# Pole_Position.net
KiCad netlist of a schematic drawn in Altium Designer
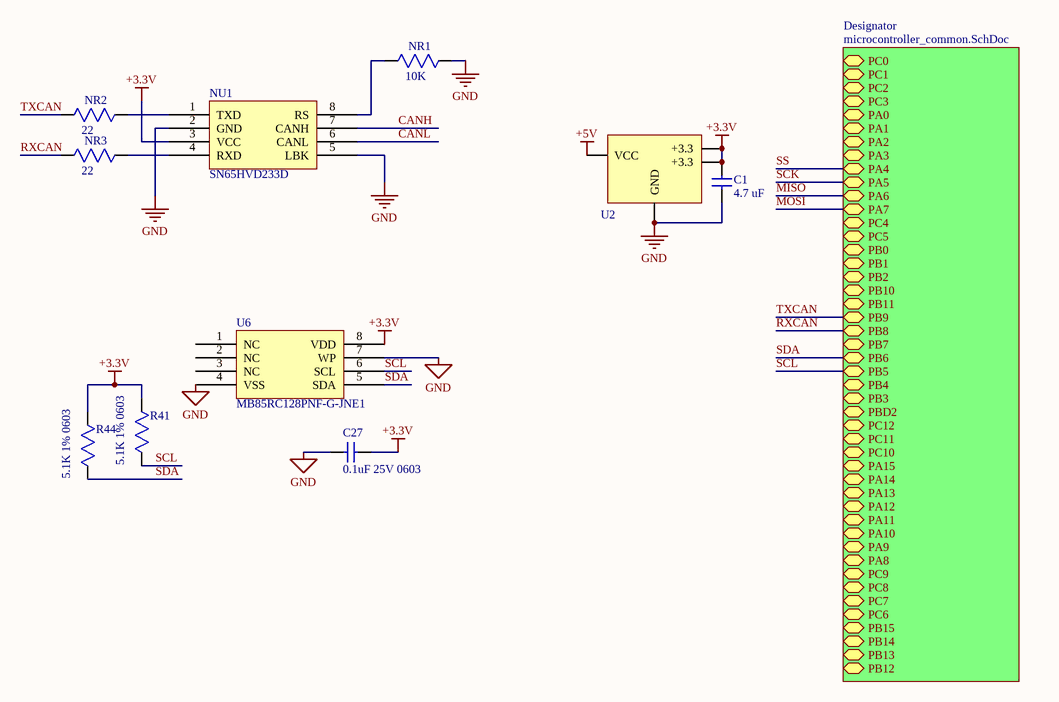
[diagram p0: Pole Position.SchDoc]

(export (version "E")
  (design (tool "Eeschema 10.0.6"))
  (components
    (comp (ref "C1")
      (value "4.7 uF")
      (footprint "0805_Capacitor")
      (description "CAP CER 4.7UF 50V X5R 10% 0805")
      (fields
        (field (name "MANUFACTURER") "TDK Corp")
        (field (name "Comment") "CAP 4.7uF")
        (field (name "SVP CREATOR") "Matt Rogge")
      )
      (libsource (lib "d1_SchLib") (part "C_0805_4.7uF"))
    )
    (comp (ref "C27")
      (value "0.1uF 25V 0603")
      (footprint "0603_cap")
      (description "CAP CER 0.1UF 25V X7R 0603")
      (fields (field (name "Comment") "CAP 0603"))
      (libsource (lib "Nutz") (part "C_0603"))
    )
    (comp (ref "NR1")
      (value "10K")
      (footprint "0805")
      (description "RES 10K OHM 1/8W 1% 0805 SMD")
      (fields (field (name "Comment") "R_0805_10k_1%") (field (name "SVP CREATOR") "Jonathan Nutzmann"))
      (libsource (lib "c3_SchLib") (part "R_0805_10K_1%"))
    )
    (comp (ref "NR2")
      (value "22")
      (footprint "0805")
      (description "RES 22 OHM 1/8W 1% 0805 SMD")
      (fields (field (name "Comment") "R_0805_22_1%") (field (name "SVP CREATOR") "Jonathan Nutzmann"))
      (libsource (lib "c3_SchLib") (part "R_0805_22_1%"))
    )
    (comp (ref "NR3")
      (value "22")
      (footprint "0805")
      (description "RES 22 OHM 1/8W 1% 0805 SMD")
      (fields (field (name "Comment") "R_0805_22_1%") (field (name "SVP CREATOR") "Jonathan Nutzmann"))
      (libsource (lib "c3_SchLib") (part "R_0805_22_1%"))
    )
    (comp (ref "NU1")
      (value "U_SN65HVD233D")
      (footprint "SOIC127P600X175-8N")
      (description "IC 3.3V CAN TXRX 8-SOIC")
      (fields (field (name "MANUFACTURER") "Texas Instruments") (field (name "PART NUMBER") "SN65HVD233D"))
      (libsource (lib "Nutz") (part "U_SN65HVD233D"))
    )
    (comp (ref "R41")
      (value "5.1K 1% 0603")
      (footprint "0603_res")
      (description "RES 5.1K 1% 0603")
      (fields (field (name "Comment") "RES 0603"))
      (libsource (lib "Nutz") (part "R_0603"))
    )
    (comp (ref "R44")
      (value "5.1K 1% 0603")
      (footprint "0603_res")
      (description "RES 5.1K 1% 0603")
      (fields (field (name "Comment") "RES 0603"))
      (libsource (lib "Nutz") (part "R_0603"))
    )
    (comp (ref "U2")
      (value "ZLDO1117G33TA")
      (footprint "SOT223-3")
      (description "IC REG LDO 1A 3.3V SOT223-3")
      (fields (field (name "MANUFACTURER") "Diodes Inc") (field (name "SVP CREATOR") "Jonathan Nutzmann"))
      (libsource (lib "d1_SchLib") (part "U_ZLDO1117G33TA"))
    )
    (comp (ref "U6")
      (value "MB85RC128PNF-G-JNE1")
      (footprint "SOIC127P600X175-8N")
      (description "IC FRAM 128KBIT 400KHZ 8SOP")
      (fields
        (field (name "MANUFACTURER") "Fujitsu Semiconductor America Inc")
        (field (name "PART NUMBER") "MB85RC128PNF-G-JNE1")
      )
      (libsource (lib "c3_SchLib") (part "U_MB85RC16PNF-G-JNE1"))
    )
  )
  (nets
    (net (code "1") (name "+3.3V") (class "Default")
      (node (ref "C1") (pin "1") (pinfunction "1_1") (pintype "passive"))
      (node (ref "C27") (pin "1") (pinfunction "1_1") (pintype "passive"))
      (node (ref "NU1") (pin "3") (pinfunction "VCC_3") (pintype "passive"))
      (node (ref "R41") (pin "1") (pinfunction "1_1") (pintype "passive"))
      (node (ref "R44") (pin "1") (pinfunction "1_1") (pintype "passive"))
      (node (ref "U2") (pin "2") (pinfunction "+3.3_2") (pintype "passive"))
      (node (ref "U2") (pin "4") (pinfunction "+3.3_4") (pintype "passive"))
      (node (ref "U6") (pin "8") (pinfunction "VDD_8") (pintype "passive"))
    )
    (net (code "2") (name "+5V") (class "Default")
      (node (ref "U2") (pin "3") (pinfunction "VCC_3") (pintype "passive"))
    )
    (net (code "3") (name "/CANH") (class "Default")
      (node (ref "NU1") (pin "7") (pinfunction "CANH_7") (pintype "passive"))
    )
    (net (code "4") (name "/CANL") (class "Default")
      (node (ref "NU1") (pin "6") (pinfunction "CANL_6") (pintype "passive"))
    )
    (net (code "45") (name "/RXCAN") (class "Default")
      (node (ref "NR3") (pin "2") (pinfunction "2_2") (pintype "passive"))
    )
    (net (code "47") (name "/SCL") (class "Default")
      (node (ref "R41") (pin "2") (pinfunction "2_2") (pintype "passive"))
      (node (ref "U6") (pin "6") (pinfunction "SCL_6") (pintype "passive"))
    )
    (net (code "48") (name "/SDA") (class "Default")
      (node (ref "R44") (pin "2") (pinfunction "2_2") (pintype "passive"))
      (node (ref "U6") (pin "5") (pinfunction "SDA_5") (pintype "passive"))
    )
    (net (code "50") (name "/TXCAN") (class "Default")
      (node (ref "NR2") (pin "2") (pinfunction "2_2") (pintype "passive"))
    )
    (net (code "51") (name "GND") (class "Default")
      (node (ref "C1") (pin "2") (pinfunction "2_2") (pintype "passive"))
      (node (ref "C27") (pin "2") (pinfunction "2_2") (pintype "passive"))
      (node (ref "NR1") (pin "1") (pinfunction "1_1") (pintype "passive"))
      (node (ref "NU1") (pin "2") (pinfunction "GND_2") (pintype "passive"))
      (node (ref "NU1") (pin "5") (pinfunction "LBK_5") (pintype "passive"))
      (node (ref "U2") (pin "1") (pinfunction "GND_1") (pintype "passive"))
      (node (ref "U6") (pin "4") (pinfunction "VSS_4") (pintype "passive"))
      (node (ref "U6") (pin "7") (pinfunction "WP_7") (pintype "passive"))
    )
    (net (code "52") (name "Net-(NU1-RS)") (class "Default")
      (node (ref "NR1") (pin "2") (pinfunction "2_2") (pintype "passive"))
      (node (ref "NU1") (pin "8") (pinfunction "RS_8") (pintype "passive"))
    )
    (net (code "53") (name "Net-(NU1-RXD)") (class "Default")
      (node (ref "NR3") (pin "1") (pinfunction "1_1") (pintype "passive"))
      (node (ref "NU1") (pin "4") (pinfunction "RXD_4") (pintype "passive"))
    )
    (net (code "54") (name "Net-(NU1-TXD)") (class "Default")
      (node (ref "NR2") (pin "1") (pinfunction "1_1") (pintype "passive"))
      (node (ref "NU1") (pin "1") (pinfunction "TXD_1") (pintype "passive"))
    )
    (net (code "55") (name "unconnected-(U6-NC-Pad1)") (class "Default")
      (node (ref "U6") (pin "1") (pinfunction "NC_1") (pintype "passive"))
    )
    (net (code "56") (name "unconnected-(U6-NC-Pad2)") (class "Default")
      (node (ref "U6") (pin "2") (pinfunction "NC_2") (pintype "passive"))
    )
    (net (code "57") (name "unconnected-(U6-NC-Pad3)") (class "Default")
      (node (ref "U6") (pin "3") (pinfunction "NC_3") (pintype "passive"))
    )
  )
)
